# SCH_AnalogAudio.net
KiCad netlist of a schematic drawn in Altium Designer
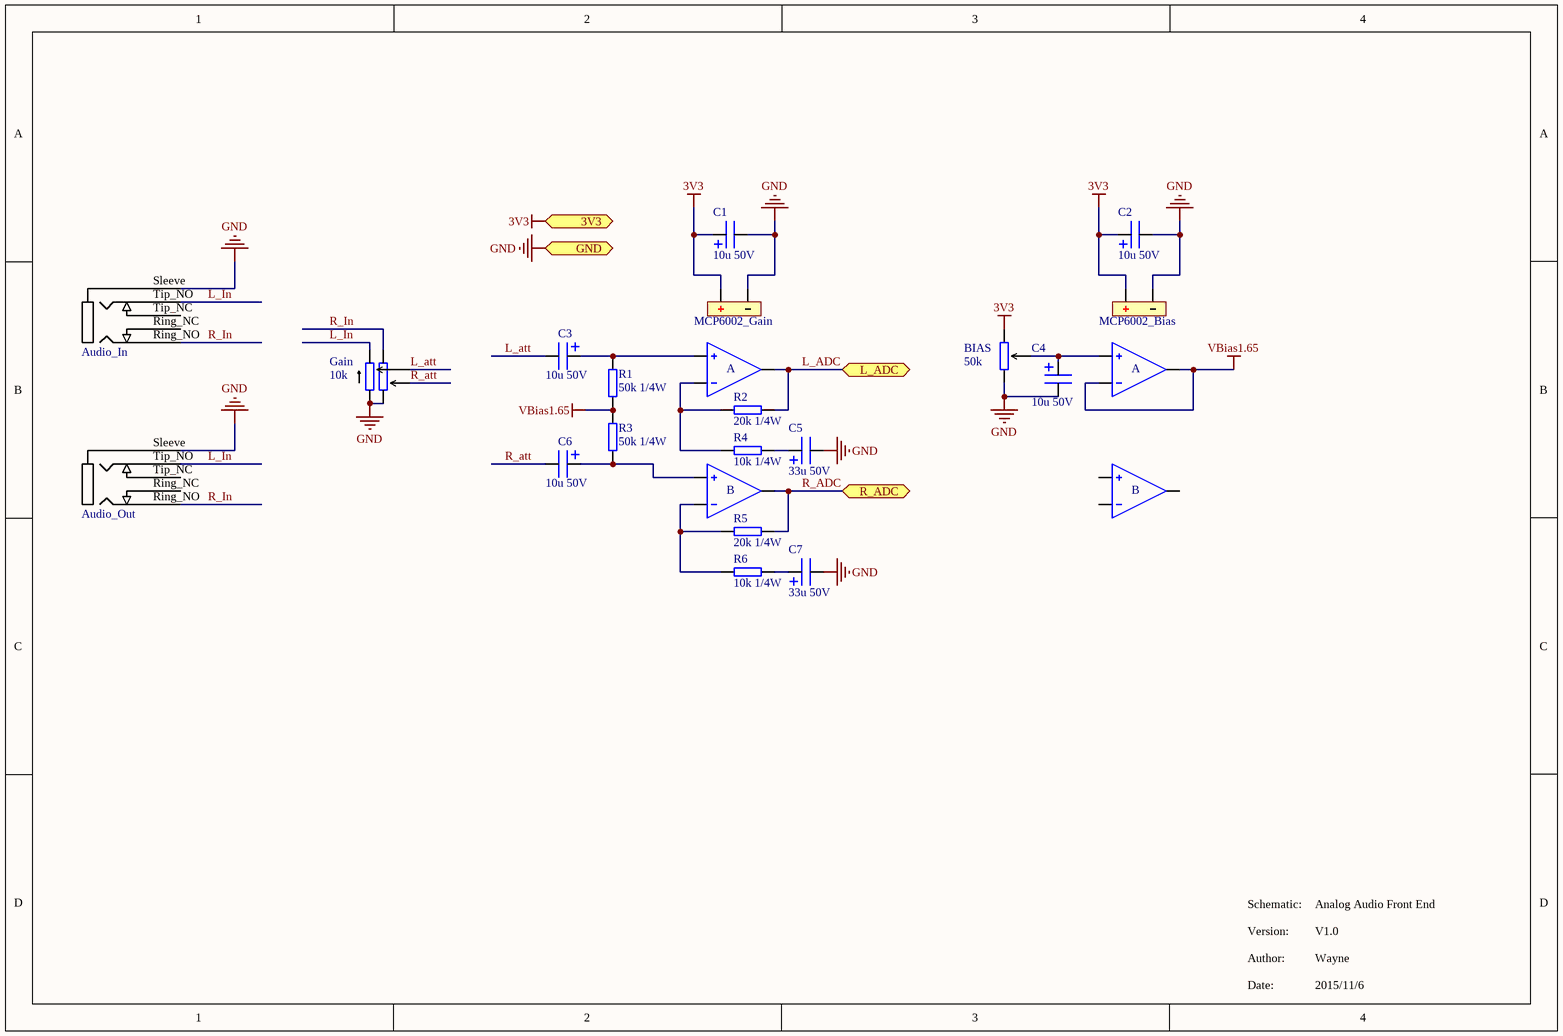
[diagram p0: SCH_AnalogAudio.SchDoc]

(export (version "E")
  (design (tool "Eeschema 10.0.6"))
  (components
    (comp (ref "Audio_In")
      (value "Generic 3.5 PhoneJack 5 Pin through-hole")
      (footprint "PCB_LIB:3.5 PhoneJack 5 Pin")
      (libsource (lib "SCH_LIB") (part "Generic 3.5 PhoneJack 5 Pin through-hole"))
    )
    (comp (ref "Audio_Out")
      (value "Generic 3.5 PhoneJack 5 Pin through-hole")
      (footprint "PCB_LIB:3.5 PhoneJack 5 Pin")
      (libsource (lib "SCH_LIB") (part "Generic 3.5 PhoneJack 5 Pin through-hole"))
    )
    (comp (ref "BIAS")
      (value "50k")
      (footprint "PCB_LIB:POT 20T")
      (description "POT 20T 3296W")
      (fields (field (name "Comment") "POT 20T"))
      (libsource (lib "SCH_LIB") (part "POT 20T 3296W"))
    )
    (comp (ref "C1")
      (value "10u 50V")
      (footprint "PCB_LIB:CAP Axial 5mm")
      (description "Axial Cap")
      (fields (field (name "Comment") "Cap"))
      (libsource (lib "SCH_LIB") (part "Axial Cap"))
    )
    (comp (ref "C2")
      (value "10u 50V")
      (footprint "PCB_LIB:CAP Axial 5mm")
      (description "Axial Cap")
      (fields (field (name "Comment") "Cap"))
      (libsource (lib "SCH_LIB") (part "Axial Cap"))
    )
    (comp (ref "C3")
      (value "10u 50V")
      (footprint "PCB_LIB:CAP Axial 5mm")
      (description "Axial Cap")
      (fields (field (name "Comment") "Cap"))
      (libsource (lib "SCH_LIB") (part "Axial Cap"))
    )
    (comp (ref "C4")
      (value "10u 50V")
      (footprint "PCB_LIB:CAP Axial 5mm")
      (description "Axial Cap")
      (fields (field (name "Comment") "Cap"))
      (libsource (lib "SCH_LIB") (part "Axial Cap"))
    )
    (comp (ref "C5")
      (value "33u 50V")
      (footprint "PCB_LIB:CAP Axial 5mm")
      (description "Axial Cap")
      (fields (field (name "Comment") "Cap"))
      (libsource (lib "SCH_LIB") (part "Axial Cap"))
    )
    (comp (ref "C6")
      (value "10u 50V")
      (footprint "PCB_LIB:CAP Axial 5mm")
      (description "Axial Cap")
      (fields (field (name "Comment") "Cap"))
      (libsource (lib "SCH_LIB") (part "Axial Cap"))
    )
    (comp (ref "C7")
      (value "33u 50V")
      (footprint "PCB_LIB:CAP Axial 5mm")
      (description "Axial Cap")
      (fields (field (name "Comment") "Cap"))
      (libsource (lib "SCH_LIB") (part "Axial Cap"))
    )
    (comp (ref "Gain")
      (value "10k")
      (footprint "PCB_LIB:POT RK09L1240A12")
      (description "ALPS POT RK09L1240A12")
      (fields (field (name "Comment") "Dual POT"))
      (libsource (lib "SCH_LIB") (part "ALPS POT RK09L1240A12"))
    )
    (comp (ref "MCP6002_Bias")
      (value "MCP6002")
      (footprint "PCB_LIB:DIP8")
      (description "MCP6002 RRIO Op Amp")
      (libsource (lib "SCH_LIB") (part "MCP6002"))
    )
    (comp (ref "MCP6002_Gain")
      (value "MCP6002")
      (footprint "PCB_LIB:DIP8")
      (description "MCP6002 RRIO Op Amp")
      (libsource (lib "SCH_LIB") (part "MCP6002"))
    )
    (comp (ref "R1")
      (value "50k 1/4W")
      (footprint "PCB_LIB:1/4W Res")
      (description "Axial Resistor")
      (fields (field (name "Comment") "Res"))
      (libsource (lib "SCH_LIB") (part "Axial Resistor"))
    )
    (comp (ref "R2")
      (value "20k 1/4W")
      (footprint "PCB_LIB:1/4W Res")
      (description "Axial Resistor")
      (fields (field (name "Comment") "Res"))
      (libsource (lib "SCH_LIB") (part "Axial Resistor"))
    )
    (comp (ref "R3")
      (value "50k 1/4W")
      (footprint "PCB_LIB:1/4W Res")
      (description "Axial Resistor")
      (fields (field (name "Comment") "Res"))
      (libsource (lib "SCH_LIB") (part "Axial Resistor"))
    )
    (comp (ref "R4")
      (value "10k 1/4W")
      (footprint "PCB_LIB:1/4W Res")
      (description "Axial Resistor")
      (fields (field (name "Comment") "Res"))
      (libsource (lib "SCH_LIB") (part "Axial Resistor"))
    )
    (comp (ref "R5")
      (value "20k 1/4W")
      (footprint "PCB_LIB:1/4W Res")
      (description "Axial Resistor")
      (fields (field (name "Comment") "Res"))
      (libsource (lib "SCH_LIB") (part "Axial Resistor"))
    )
    (comp (ref "R6")
      (value "10k 1/4W")
      (footprint "PCB_LIB:1/4W Res")
      (description "Axial Resistor")
      (fields (field (name "Comment") "Res"))
      (libsource (lib "SCH_LIB") (part "Axial Resistor"))
    )
  )
  (nets
    (net (code "1") (name "/L_ADC") (class "Default")
      (node (ref "MCP6002_Gain") (pin "1") (pinfunction "VOUTA_1") (pintype "passive"))
      (node (ref "R2") (pin "1") (pinfunction "1_1") (pintype "passive"))
    )
    (net (code "2") (name "/L_In") (class "Default")
      (node (ref "Audio_In") (pin "Tip_NO") (pinfunction "Tip_NO_Tip_NO") (pintype "passive"))
      (node (ref "Audio_Out") (pin "Tip_NO") (pinfunction "Tip_NO_Tip_NO") (pintype "passive"))
      (node (ref "Gain") (pin "A3") (pinfunction "A3_A3") (pintype "passive"))
    )
    (net (code "3") (name "/L_att") (class "Default")
      (node (ref "C3") (pin "1") (pinfunction "1_1") (pintype "passive"))
      (node (ref "Gain") (pin "A2") (pinfunction "A2_A2") (pintype "passive"))
    )
    (net (code "4") (name "/R_ADC") (class "Default")
      (node (ref "MCP6002_Gain") (pin "7") (pinfunction "VOUTB_7") (pintype "passive"))
      (node (ref "R5") (pin "1") (pinfunction "1_1") (pintype "passive"))
    )
    (net (code "5") (name "/R_In") (class "Default")
      (node (ref "Audio_In") (pin "Ring_NO") (pinfunction "Ring_NO_Ring_NO") (pintype "passive"))
      (node (ref "Audio_Out") (pin "Ring_NO") (pinfunction "Ring_NO_Ring_NO") (pintype "passive"))
      (node (ref "Gain") (pin "B3") (pinfunction "B3_B3") (pintype "passive"))
    )
    (net (code "6") (name "/R_att") (class "Default")
      (node (ref "C6") (pin "1") (pinfunction "1_1") (pintype "passive"))
      (node (ref "Gain") (pin "B2") (pinfunction "B2_B2") (pintype "passive"))
    )
    (net (code "7") (name "3V3") (class "Default")
      (node (ref "BIAS") (pin "3") (pinfunction "3_3") (pintype "passive"))
      (node (ref "C1") (pin "2") (pinfunction "2_2") (pintype "passive"))
      (node (ref "C2") (pin "2") (pinfunction "2_2") (pintype "passive"))
      (node (ref "MCP6002_Bias") (pin "8") (pinfunction "VDD_8") (pintype "passive"))
      (node (ref "MCP6002_Gain") (pin "8") (pinfunction "VDD_8") (pintype "passive"))
    )
    (net (code "8") (name "GND") (class "Default")
      (node (ref "Audio_In") (pin "Sleeve") (pinfunction "Sleeve_Sleeve") (pintype "passive"))
      (node (ref "Audio_Out") (pin "Sleeve") (pinfunction "Sleeve_Sleeve") (pintype "passive"))
      (node (ref "BIAS") (pin "1") (pinfunction "1_1") (pintype "passive"))
      (node (ref "C1") (pin "1") (pinfunction "1_1") (pintype "passive"))
      (node (ref "C2") (pin "1") (pinfunction "1_1") (pintype "passive"))
      (node (ref "C4") (pin "1") (pinfunction "1_1") (pintype "passive"))
      (node (ref "C5") (pin "1") (pinfunction "1_1") (pintype "passive"))
      (node (ref "C7") (pin "1") (pinfunction "1_1") (pintype "passive"))
      (node (ref "Gain") (pin "A1") (pinfunction "A1_A1") (pintype "passive"))
      (node (ref "Gain") (pin "B1") (pinfunction "B1_B1") (pintype "passive"))
      (node (ref "MCP6002_Bias") (pin "4") (pinfunction "VSS_4") (pintype "passive"))
      (node (ref "MCP6002_Gain") (pin "4") (pinfunction "VSS_4") (pintype "passive"))
    )
    (net (code "9") (name "Net-(C5-Pad2)") (class "Default")
      (node (ref "C5") (pin "2") (pinfunction "2_2") (pintype "passive"))
      (node (ref "R4") (pin "1") (pinfunction "1_1") (pintype "passive"))
    )
    (net (code "10") (name "Net-(C7-Pad2)") (class "Default")
      (node (ref "C7") (pin "2") (pinfunction "2_2") (pintype "passive"))
      (node (ref "R6") (pin "1") (pinfunction "1_1") (pintype "passive"))
    )
    (net (code "11") (name "Net-(MCP6002_Bias-VINA+)") (class "Default")
      (node (ref "BIAS") (pin "2") (pinfunction "2_2") (pintype "passive"))
      (node (ref "C4") (pin "2") (pinfunction "2_2") (pintype "passive"))
      (node (ref "MCP6002_Bias") (pin "3") (pinfunction "VINA+_3") (pintype "passive"))
    )
    (net (code "12") (name "Net-(MCP6002_Gain-VINA+)") (class "Default")
      (node (ref "C3") (pin "2") (pinfunction "2_2") (pintype "passive"))
      (node (ref "MCP6002_Gain") (pin "3") (pinfunction "VINA+_3") (pintype "passive"))
      (node (ref "R1") (pin "2") (pinfunction "2_2") (pintype "passive"))
    )
    (net (code "13") (name "Net-(MCP6002_Gain-VINA-)") (class "Default")
      (node (ref "MCP6002_Gain") (pin "2") (pinfunction "VINA-_2") (pintype "passive"))
      (node (ref "R2") (pin "2") (pinfunction "2_2") (pintype "passive"))
      (node (ref "R4") (pin "2") (pinfunction "2_2") (pintype "passive"))
    )
    (net (code "14") (name "Net-(MCP6002_Gain-VINB+)") (class "Default")
      (node (ref "C6") (pin "2") (pinfunction "2_2") (pintype "passive"))
      (node (ref "MCP6002_Gain") (pin "5") (pinfunction "VINB+_5") (pintype "passive"))
      (node (ref "R3") (pin "1") (pinfunction "1_1") (pintype "passive"))
    )
    (net (code "15") (name "Net-(MCP6002_Gain-VINB-)") (class "Default")
      (node (ref "MCP6002_Gain") (pin "6") (pinfunction "VINB-_6") (pintype "passive"))
      (node (ref "R5") (pin "2") (pinfunction "2_2") (pintype "passive"))
      (node (ref "R6") (pin "2") (pinfunction "2_2") (pintype "passive"))
    )
    (net (code "16") (name "VBias1.65") (class "Default")
      (node (ref "MCP6002_Bias") (pin "1") (pinfunction "VOUTA_1") (pintype "passive"))
      (node (ref "MCP6002_Bias") (pin "2") (pinfunction "VINA-_2") (pintype "passive"))
      (node (ref "R1") (pin "1") (pinfunction "1_1") (pintype "passive"))
      (node (ref "R3") (pin "2") (pinfunction "2_2") (pintype "passive"))
    )
    (net (code "17") (name "unconnected-(Audio_In-PadRing_NC)") (class "Default")
      (node (ref "Audio_In") (pin "Ring_NC") (pinfunction "Ring_NC_Ring_NC") (pintype "passive"))
    )
    (net (code "18") (name "unconnected-(Audio_In-PadTip_NC)") (class "Default")
      (node (ref "Audio_In") (pin "Tip_NC") (pinfunction "Tip_NC_Tip_NC") (pintype "passive"))
    )
    (net (code "19") (name "unconnected-(Audio_Out-PadRing_NC)") (class "Default")
      (node (ref "Audio_Out") (pin "Ring_NC") (pinfunction "Ring_NC_Ring_NC") (pintype "passive"))
    )
    (net (code "20") (name "unconnected-(Audio_Out-PadTip_NC)") (class "Default")
      (node (ref "Audio_Out") (pin "Tip_NC") (pinfunction "Tip_NC_Tip_NC") (pintype "passive"))
    )
    (net (code "21") (name "unconnected-(MCP6002_Bias-VINB+-Pad5)") (class "Default")
      (node (ref "MCP6002_Bias") (pin "5") (pinfunction "VINB+_5") (pintype "passive"))
    )
    (net (code "22") (name "unconnected-(MCP6002_Bias-VINB--Pad6)") (class "Default")
      (node (ref "MCP6002_Bias") (pin "6") (pinfunction "VINB-_6") (pintype "passive"))
    )
    (net (code "23") (name "unconnected-(MCP6002_Bias-VOUTB-Pad7)") (class "Default")
      (node (ref "MCP6002_Bias") (pin "7") (pinfunction "VOUTB_7") (pintype "passive"))
    )
  )
)
